# IR_Schreib_Lesekopf_RS232_Neu.net
KiCad netlist of a schematic drawn in EAGLE
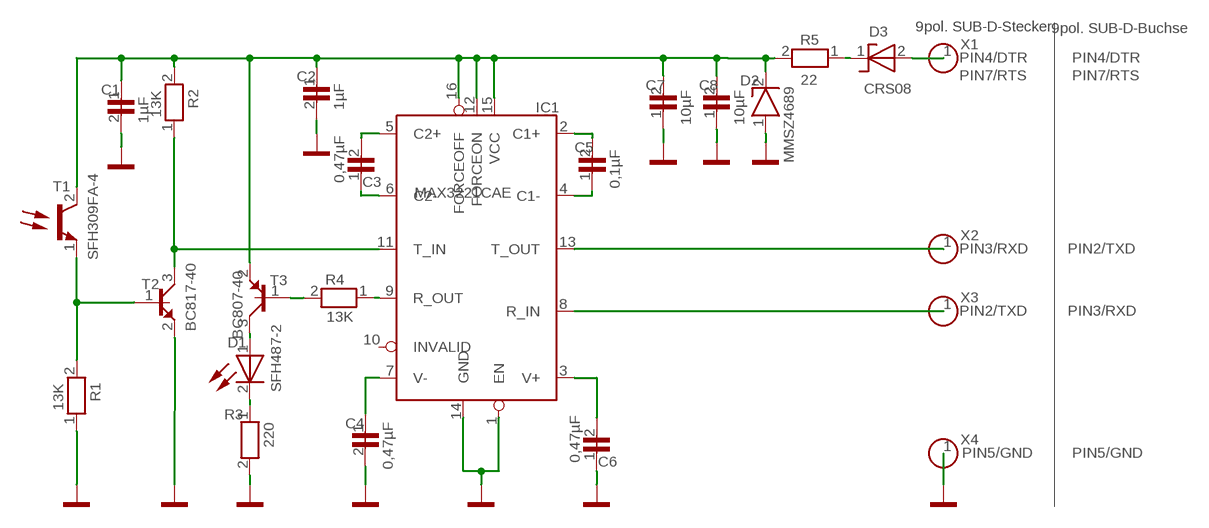
[diagram p0: schematic, sheet 1]

(export (version "E")
  (design (tool "Eeschema 10.0.6"))
  (components
    (comp (ref "C1")
      (value "1µF")
      (footprint "eagle-import:0603_KLEIN")
      (libsource (lib "eagle-import") (part "1µF"))
    )
    (comp (ref "C2")
      (value "1µF")
      (footprint "eagle-import:0603_KLEIN")
      (libsource (lib "eagle-import") (part "1µF"))
    )
    (comp (ref "C3")
      (value "0,47µF")
      (footprint "eagle-import:0603")
      (libsource (lib "eagle-import") (part "0,47µF"))
    )
    (comp (ref "C4")
      (value "0,47µF")
      (footprint "eagle-import:0603")
      (libsource (lib "eagle-import") (part "0,47µF"))
    )
    (comp (ref "C5")
      (value "0,1µF")
      (footprint "eagle-import:0603")
      (libsource (lib "eagle-import") (part "0,1µF"))
    )
    (comp (ref "C6")
      (value "0,47µF")
      (footprint "eagle-import:0603")
      (libsource (lib "eagle-import") (part "0,47µF"))
    )
    (comp (ref "C7")
      (value "10µF")
      (footprint "eagle-import:0805_KLEIN")
      (libsource (lib "eagle-import") (part "10µF"))
    )
    (comp (ref "C8")
      (value "10µF")
      (footprint "eagle-import:0805_KLEIN")
      (libsource (lib "eagle-import") (part "10µF"))
    )
    (comp (ref "D1")
      (value "SFH487-2")
      (footprint "eagle-import:LED_3MM")
      (libsource (lib "eagle-import") (part "SFH487-2"))
    )
    (comp (ref "D2")
      (value "MMSZ4689")
      (footprint "eagle-import:SOD123")
      (libsource (lib "eagle-import") (part "MMSZ4689"))
    )
    (comp (ref "D3")
      (value "CRS08")
      (footprint "eagle-import:SOD123")
      (libsource (lib "eagle-import") (part "CRS08"))
    )
    (comp (ref "IC1")
      (value "MAX3221CAE")
      (footprint "eagle-import:SSOP16")
      (libsource (lib "eagle-import") (part "MAX3221CAE"))
    )
    (comp (ref "R1")
      (value "13K")
      (footprint "eagle-import:0603_KLEIN")
      (libsource (lib "eagle-import") (part "13K"))
    )
    (comp (ref "R2")
      (value "13K")
      (footprint "eagle-import:0603_KLEIN")
      (libsource (lib "eagle-import") (part "13K"))
    )
    (comp (ref "R3")
      (value "220")
      (footprint "eagle-import:0603_KLEIN")
      (libsource (lib "eagle-import") (part "220"))
    )
    (comp (ref "R4")
      (value "13K")
      (footprint "eagle-import:0603_KLEIN")
      (libsource (lib "eagle-import") (part "13K"))
    )
    (comp (ref "R5")
      (value "22")
      (footprint "eagle-import:1206")
      (libsource (lib "eagle-import") (part "22"))
    )
    (comp (ref "T1")
      (value "SFH309FA-4")
      (footprint "eagle-import:LED_3MM")
      (libsource (lib "eagle-import") (part "SFH309FA-4"))
    )
    (comp (ref "T2")
      (value "BC817-40")
      (footprint "eagle-import:SOT23_3")
      (libsource (lib "eagle-import") (part "BC817-40"))
    )
    (comp (ref "T3")
      (value "BC807-40")
      (footprint "eagle-import:SOT23_3")
      (libsource (lib "eagle-import") (part "BC807-40"))
    )
    (comp (ref "X1")
      (value "PIN4/DTR")
      (footprint "eagle-import:LOETPUNKT")
      (libsource (lib "eagle-import") (part "PIN4/DTR"))
    )
    (comp (ref "X2")
      (value "PIN3/RXD")
      (footprint "eagle-import:LOETPUNKT")
      (libsource (lib "eagle-import") (part "PIN3/RXD"))
    )
    (comp (ref "X3")
      (value "PIN2/TXD")
      (footprint "eagle-import:LOETPUNKT")
      (libsource (lib "eagle-import") (part "PIN2/TXD"))
    )
    (comp (ref "X4")
      (value "PIN5/GND")
      (footprint "eagle-import:LOETPUNKT")
      (libsource (lib "eagle-import") (part "PIN5/GND"))
    )
  )
  (nets
    (net (code "1") (name "GND") (class "Default")
      (node (ref "C1") (pin "2") (pinfunction "2_2") (pintype "passive"))
      (node (ref "C2") (pin "2") (pinfunction "2_2") (pintype "passive"))
      (node (ref "C4") (pin "2") (pinfunction "2_2") (pintype "passive"))
      (node (ref "C6") (pin "1") (pinfunction "1_1") (pintype "passive"))
      (node (ref "C7") (pin "1") (pinfunction "1_1") (pintype "passive"))
      (node (ref "C8") (pin "1") (pinfunction "1_1") (pintype "passive"))
      (node (ref "D2") (pin "1") (pinfunction "1_1") (pintype "passive"))
      (node (ref "IC1") (pin "1") (pinfunction "EN_1") (pintype "input"))
      (node (ref "IC1") (pin "14") (pinfunction "GND_14") (pintype "power_in"))
      (node (ref "R1") (pin "1") (pinfunction "1_1") (pintype "passive"))
      (node (ref "R3") (pin "2") (pinfunction "2_2") (pintype "passive"))
      (node (ref "T2") (pin "2") (pinfunction "2_2") (pintype "passive"))
      (node (ref "X4") (pin "1") (pinfunction "1_1") (pintype "passive"))
    )
    (net (code "2") (name "Net-(D1-Pad1)") (class "Default")
      (node (ref "D1") (pin "1") (pinfunction "1_1") (pintype "passive"))
      (node (ref "T3") (pin "3") (pinfunction "3_3") (pintype "passive"))
    )
    (net (code "3") (name "Net-(D1-Pad2)") (class "Default")
      (node (ref "D1") (pin "2") (pinfunction "2_2") (pintype "passive"))
      (node (ref "R3") (pin "1") (pinfunction "1_1") (pintype "passive"))
    )
    (net (code "4") (name "Net-(D3-Pad1)") (class "Default")
      (node (ref "D3") (pin "1") (pinfunction "1_1") (pintype "passive"))
      (node (ref "R5") (pin "1") (pinfunction "1_1") (pintype "passive"))
    )
    (net (code "5") (name "Net-(D3-Pad2)") (class "Default")
      (node (ref "D3") (pin "2") (pinfunction "2_2") (pintype "passive"))
      (node (ref "X1") (pin "1") (pinfunction "1_1") (pintype "passive"))
    )
    (net (code "6") (name "Net-(IC1-C1+)") (class "Default")
      (node (ref "C5") (pin "2") (pinfunction "2_2") (pintype "passive"))
      (node (ref "IC1") (pin "2") (pinfunction "C1+_2") (pintype "passive"))
    )
    (net (code "7") (name "Net-(IC1-C1-)") (class "Default")
      (node (ref "C5") (pin "1") (pinfunction "1_1") (pintype "passive"))
      (node (ref "IC1") (pin "4") (pinfunction "C1-_4") (pintype "passive"))
    )
    (net (code "8") (name "Net-(IC1-C2+)") (class "Default")
      (node (ref "C3") (pin "2") (pinfunction "2_2") (pintype "passive"))
      (node (ref "IC1") (pin "5") (pinfunction "C2+_5") (pintype "passive"))
    )
    (net (code "9") (name "Net-(IC1-C2-)") (class "Default")
      (node (ref "C3") (pin "1") (pinfunction "1_1") (pintype "passive"))
      (node (ref "IC1") (pin "6") (pinfunction "C2-_6") (pintype "passive"))
    )
    (net (code "10") (name "Net-(IC1-FORCEOFF)") (class "Default")
      (node (ref "C1") (pin "1") (pinfunction "1_1") (pintype "passive"))
      (node (ref "C2") (pin "1") (pinfunction "1_1") (pintype "passive"))
      (node (ref "C7") (pin "2") (pinfunction "2_2") (pintype "passive"))
      (node (ref "C8") (pin "2") (pinfunction "2_2") (pintype "passive"))
      (node (ref "D2") (pin "2") (pinfunction "2_2") (pintype "passive"))
      (node (ref "IC1") (pin "12") (pinfunction "FORCEON_12") (pintype "passive"))
      (node (ref "IC1") (pin "15") (pinfunction "VCC_15") (pintype "power_in"))
      (node (ref "IC1") (pin "16") (pinfunction "FORCEOFF_16") (pintype "passive"))
      (node (ref "R2") (pin "2") (pinfunction "2_2") (pintype "passive"))
      (node (ref "R5") (pin "2") (pinfunction "2_2") (pintype "passive"))
      (node (ref "T1") (pin "2") (pinfunction "2_2") (pintype "passive"))
      (node (ref "T3") (pin "2") (pinfunction "2_2") (pintype "passive"))
    )
    (net (code "11") (name "Net-(IC1-R_IN)") (class "Default")
      (node (ref "IC1") (pin "8") (pinfunction "R_IN_8") (pintype "input"))
      (node (ref "X3") (pin "1") (pinfunction "1_1") (pintype "passive"))
    )
    (net (code "12") (name "Net-(IC1-R_OUT)") (class "Default")
      (node (ref "IC1") (pin "9") (pinfunction "R_OUT_9") (pintype "output"))
      (node (ref "R4") (pin "1") (pinfunction "1_1") (pintype "passive"))
    )
    (net (code "13") (name "Net-(IC1-T_IN)") (class "Default")
      (node (ref "IC1") (pin "11") (pinfunction "T_IN_11") (pintype "input"))
      (node (ref "R2") (pin "1") (pinfunction "1_1") (pintype "passive"))
      (node (ref "T2") (pin "3") (pinfunction "3_3") (pintype "passive"))
    )
    (net (code "14") (name "Net-(IC1-T_OUT)") (class "Default")
      (node (ref "IC1") (pin "13") (pinfunction "T_OUT_13") (pintype "output"))
      (node (ref "X2") (pin "1") (pinfunction "1_1") (pintype "passive"))
    )
    (net (code "15") (name "Net-(IC1-V+)") (class "Default")
      (node (ref "C6") (pin "2") (pinfunction "2_2") (pintype "passive"))
      (node (ref "IC1") (pin "3") (pinfunction "V+_3") (pintype "power_in"))
    )
    (net (code "16") (name "Net-(IC1-V-)") (class "Default")
      (node (ref "C4") (pin "1") (pinfunction "1_1") (pintype "passive"))
      (node (ref "IC1") (pin "7") (pinfunction "V-_7") (pintype "power_in"))
    )
    (net (code "17") (name "Net-(R1-Pad2)") (class "Default")
      (node (ref "R1") (pin "2") (pinfunction "2_2") (pintype "passive"))
      (node (ref "T1") (pin "1") (pinfunction "1_1") (pintype "passive"))
      (node (ref "T2") (pin "1") (pinfunction "1_1") (pintype "passive"))
    )
    (net (code "18") (name "Net-(R4-Pad2)") (class "Default")
      (node (ref "R4") (pin "2") (pinfunction "2_2") (pintype "passive"))
      (node (ref "T3") (pin "1") (pinfunction "1_1") (pintype "passive"))
    )
    (net (code "19") (name "unconnected-(IC1-INVALID-Pad10)") (class "Default")
      (node (ref "IC1") (pin "10") (pinfunction "INVALID_10") (pintype "output"))
    )
  )
)
